# Sensly_HAT_v1_6.net
KiCad netlist of a schematic drawn in EAGLE
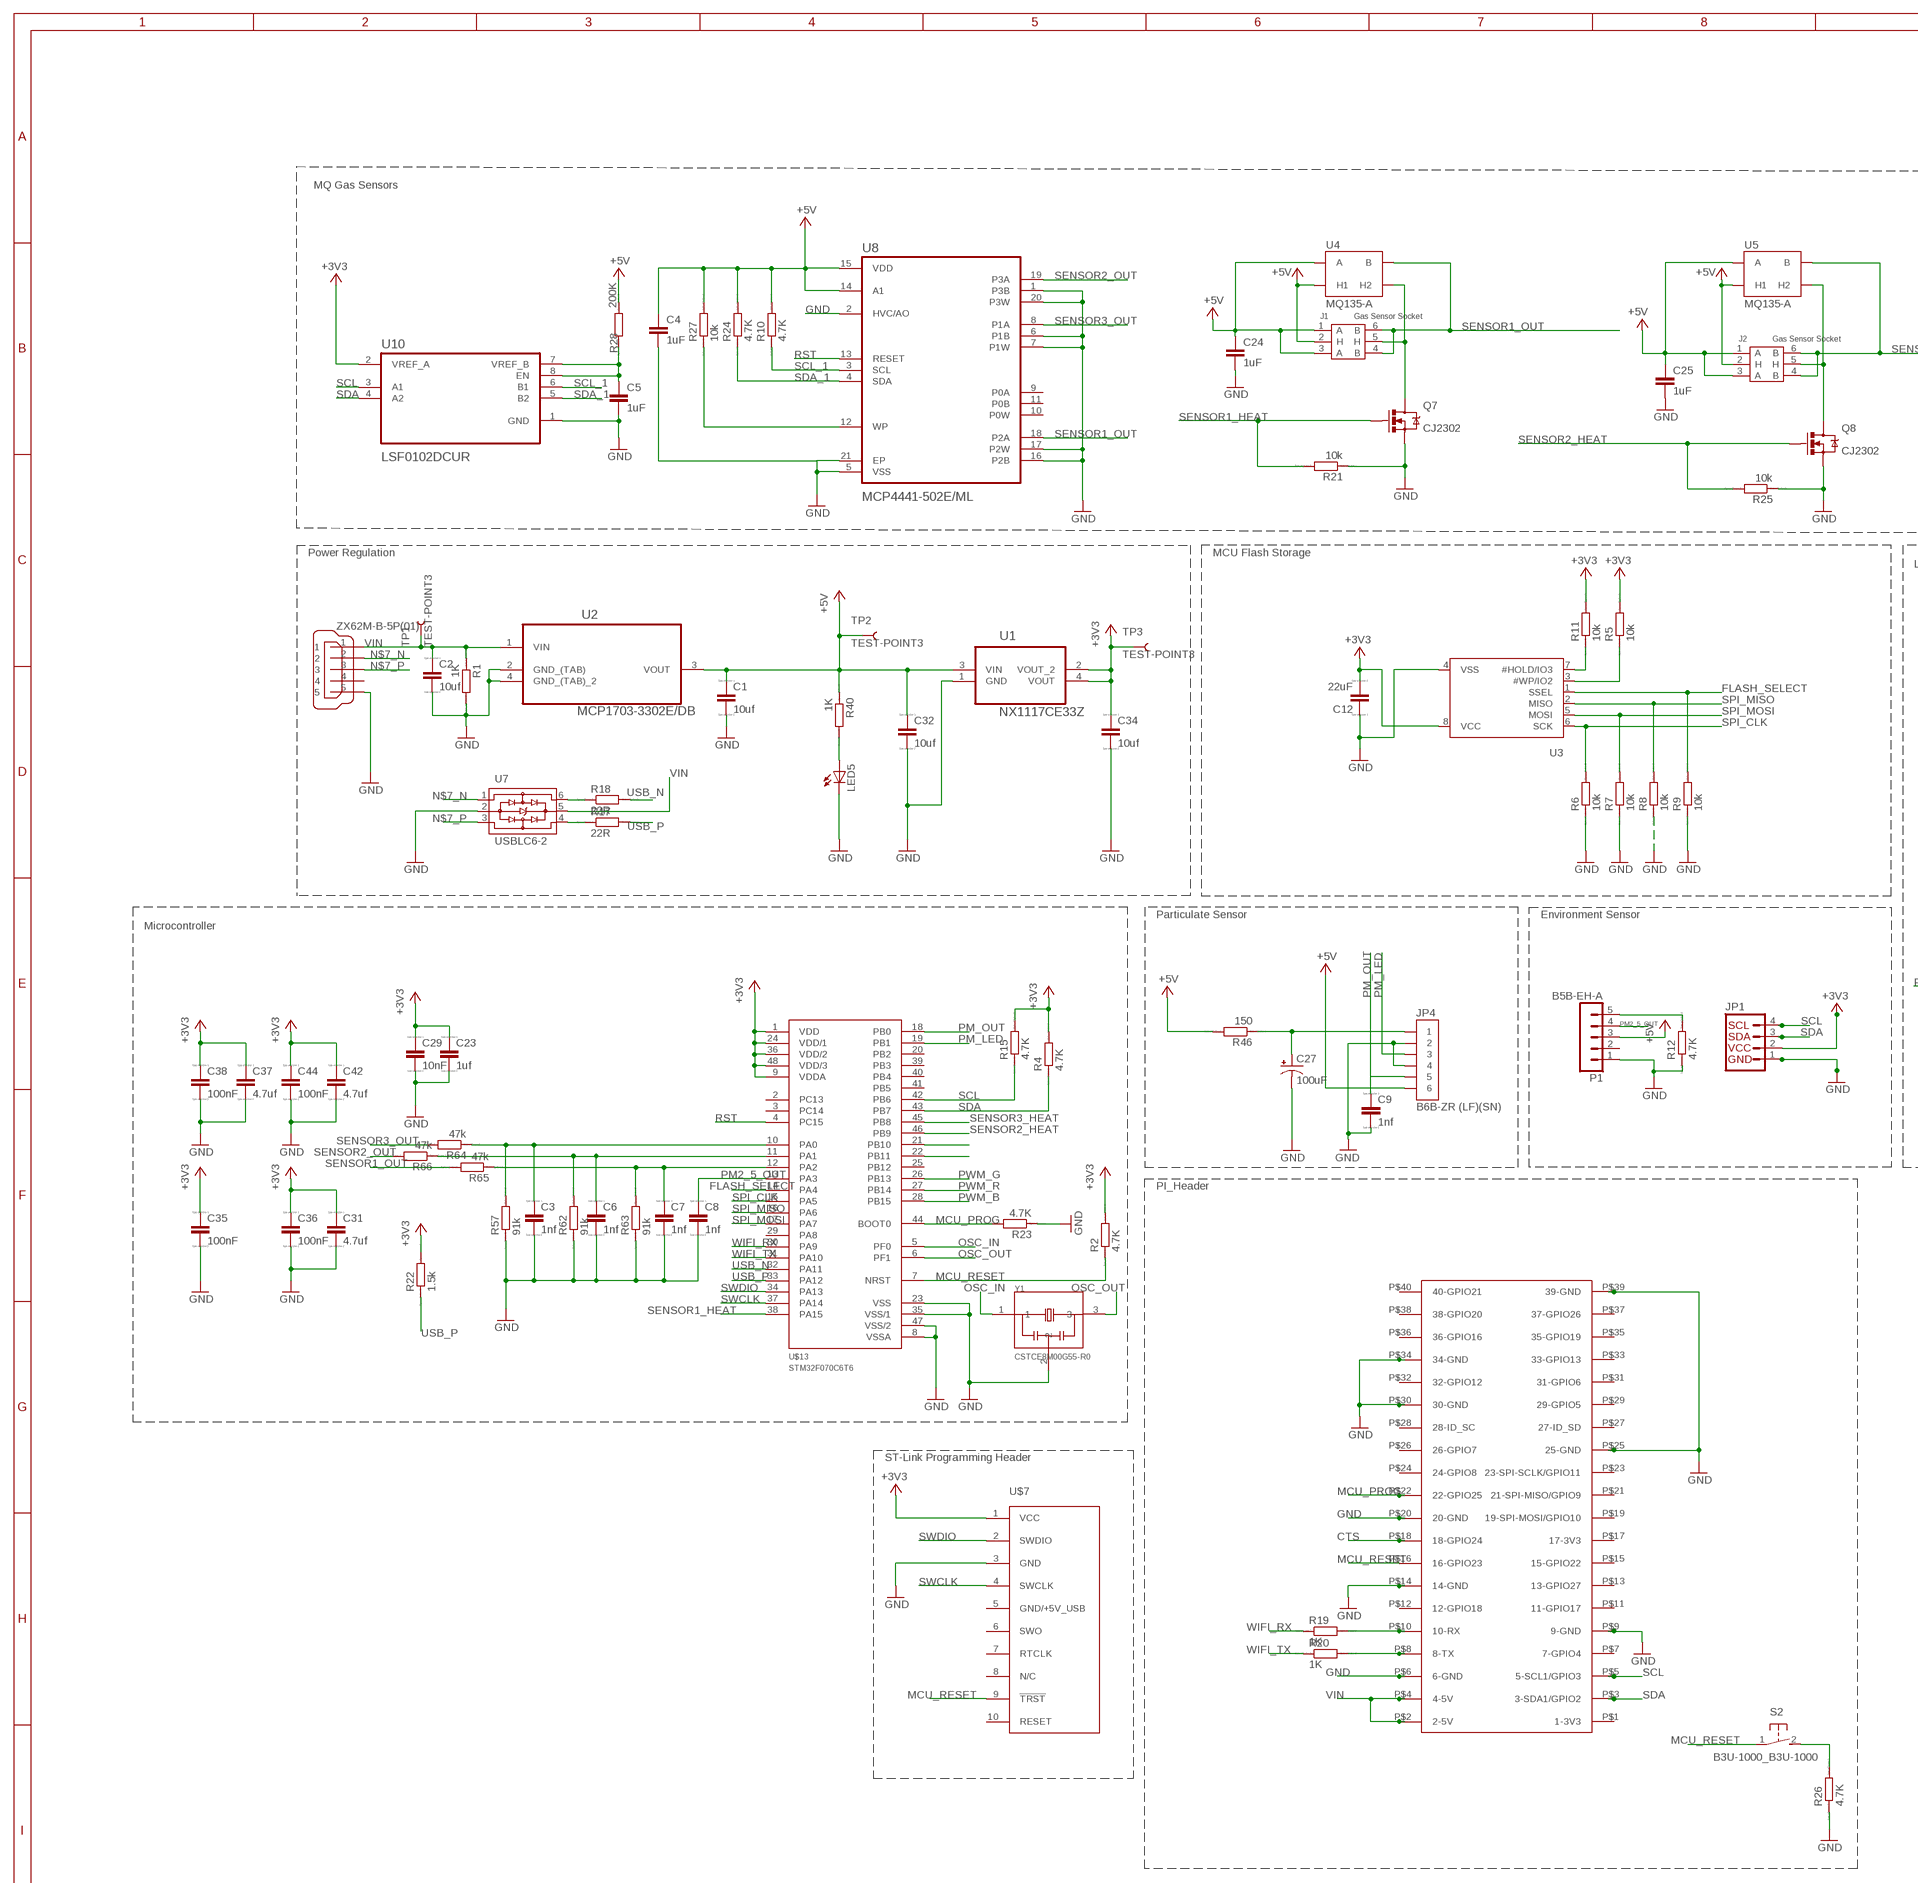
[diagram p0: schematic, sheet 1, part 1 of 2]
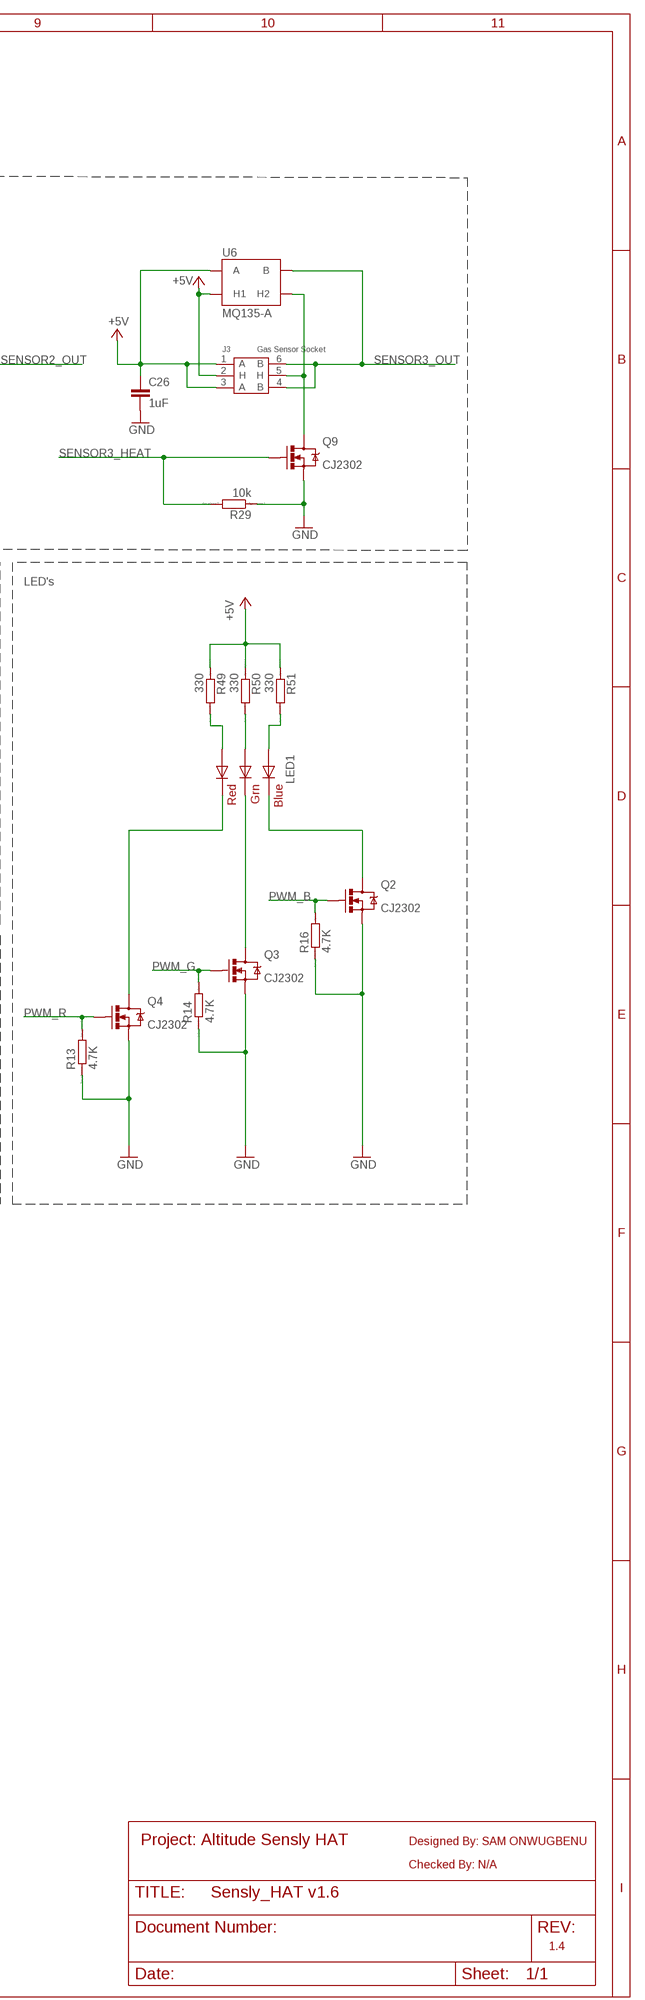
[diagram p1: schematic, sheet 1, part 2 of 2]

(export (version "E")
  (design (tool "Eeschema 10.0.6"))
  (components
    (comp (ref "C1")
      (value "10uf")
      (footprint "eagle-import:C0603")
      (libsource (lib "eagle-import") (part "CC0603"))
    )
    (comp (ref "C2")
      (value "10uf")
      (footprint "eagle-import:C0603")
      (libsource (lib "eagle-import") (part "CC0603"))
    )
    (comp (ref "C3")
      (value "1nf")
      (footprint "eagle-import:EAGLE-LTSPICE_C0402")
      (libsource (lib "eagle-import") (part "EAGLE-LTSPICE_CC0402"))
    )
    (comp (ref "C4")
      (value "1uF")
      (footprint "eagle-import:0603_N")
      (libsource (lib "eagle-import") (part "C0603"))
    )
    (comp (ref "C5")
      (value "1uF")
      (footprint "eagle-import:0603_N")
      (libsource (lib "eagle-import") (part "C0603"))
    )
    (comp (ref "C6")
      (value "1nf")
      (footprint "eagle-import:EAGLE-LTSPICE_C0402")
      (libsource (lib "eagle-import") (part "EAGLE-LTSPICE_CC0402"))
    )
    (comp (ref "C7")
      (value "1nf")
      (footprint "eagle-import:EAGLE-LTSPICE_C0402")
      (libsource (lib "eagle-import") (part "EAGLE-LTSPICE_CC0402"))
    )
    (comp (ref "C8")
      (value "1nf")
      (footprint "eagle-import:EAGLE-LTSPICE_C0402")
      (libsource (lib "eagle-import") (part "EAGLE-LTSPICE_CC0402"))
    )
    (comp (ref "C9")
      (value "1nf")
      (footprint "eagle-import:EAGLE-LTSPICE_C0402")
      (libsource (lib "eagle-import") (part "EAGLE-LTSPICE_CC0402"))
    )
    (comp (ref "C12")
      (value "22uF")
      (footprint "eagle-import:C0603")
      (libsource (lib "eagle-import") (part "CC0603"))
    )
    (comp (ref "C23")
      (value "1uf")
      (footprint "eagle-import:C0603")
      (libsource (lib "eagle-import") (part "CC0603"))
    )
    (comp (ref "C24")
      (value "1uF")
      (footprint "eagle-import:0603_N")
      (libsource (lib "eagle-import") (part "C0603"))
    )
    (comp (ref "C25")
      (value "1uF")
      (footprint "eagle-import:0603_N")
      (libsource (lib "eagle-import") (part "C0603"))
    )
    (comp (ref "C26")
      (value "1uF")
      (footprint "eagle-import:0603_N")
      (libsource (lib "eagle-import") (part "C0603"))
    )
    (comp (ref "C27")
      (value "100uF")
      (footprint "eagle-import:EIA3216")
      (libsource (lib "eagle-import") (part "CAP_POL1206"))
    )
    (comp (ref "C29")
      (value "10nF")
      (footprint "eagle-import:C0603")
      (libsource (lib "eagle-import") (part "CC0603"))
    )
    (comp (ref "C31")
      (value "4.7uf")
      (footprint "eagle-import:C0603")
      (libsource (lib "eagle-import") (part "CC0603"))
    )
    (comp (ref "C32")
      (value "10uf")
      (footprint "eagle-import:C0603")
      (libsource (lib "eagle-import") (part "CC0603"))
    )
    (comp (ref "C34")
      (value "10uf")
      (footprint "eagle-import:C0603")
      (libsource (lib "eagle-import") (part "CC0603"))
    )
    (comp (ref "C35")
      (value "100nF")
      (footprint "eagle-import:C0603")
      (libsource (lib "eagle-import") (part "CC0603"))
    )
    (comp (ref "C36")
      (value "100nF")
      (footprint "eagle-import:C0603")
      (libsource (lib "eagle-import") (part "CC0603"))
    )
    (comp (ref "C37")
      (value "4.7uf")
      (footprint "eagle-import:C0603")
      (libsource (lib "eagle-import") (part "CC0603"))
    )
    (comp (ref "C38")
      (value "100nF")
      (footprint "eagle-import:C0603")
      (libsource (lib "eagle-import") (part "CC0603"))
    )
    (comp (ref "C42")
      (value "4.7uf")
      (footprint "eagle-import:C0603")
      (libsource (lib "eagle-import") (part "CC0603"))
    )
    (comp (ref "C44")
      (value "100nF")
      (footprint "eagle-import:C0603")
      (libsource (lib "eagle-import") (part "CC0603"))
    )
    (comp (ref "J1")
      (value "Gas Sensor Socket")
      (footprint "eagle-import:6P-D17.6X9.8H")
      (libsource (lib "eagle-import") (part "MQ-SOCKET"))
    )
    (comp (ref "J2")
      (value "Gas Sensor Socket")
      (footprint "eagle-import:6P-D17.6X9.8H")
      (libsource (lib "eagle-import") (part "MQ-SOCKET"))
    )
    (comp (ref "J3")
      (value "Gas Sensor Socket")
      (footprint "eagle-import:6P-D17.6X9.8H")
      (libsource (lib "eagle-import") (part "MQ-SOCKET"))
    )
    (comp (ref "JP1")
      (value "I2C_STANDARD")
      (footprint "eagle-import:1X04")
      (libsource (lib "eagle-import") (part "I2C_STANDARD"))
    )
    (comp (ref "JP4")
      (value "B6B-ZR (LF)(SN)")
      (footprint "eagle-import:CONNECTOR_B6B-ZR")
      (libsource (lib "eagle-import") (part "CONNECTOR_6X1-ZR-THT"))
    )
    (comp (ref "LED1")
      (value "RGBLED5050")
      (footprint "eagle-import:RGBLED5050")
      (libsource (lib "eagle-import") (part "RGBLED5050"))
    )
    (comp (ref "LED5")
      (value "LEDCHIPLED_0603")
      (footprint "eagle-import:CHIPLED_0603")
      (libsource (lib "eagle-import") (part "LEDCHIPLED_0603"))
    )
    (comp (ref "P1")
      (value "B5B-EH-A")
      (footprint "eagle-import:B5B-EH-A")
      (libsource (lib "eagle-import") (part "B5B-EH-A"))
    )
    (comp (ref "Q2")
      (value "CJ2302")
      (footprint "eagle-import:SOT-23-3_N_SSOT-3_N")
      (libsource (lib "eagle-import") (part "MOSFET_N_SOT23-3"))
    )
    (comp (ref "Q3")
      (value "CJ2302")
      (footprint "eagle-import:SOT-23-3_N_SSOT-3_N")
      (libsource (lib "eagle-import") (part "MOSFET_N_SOT23-3"))
    )
    (comp (ref "Q4")
      (value "CJ2302")
      (footprint "eagle-import:SOT-23-3_N_SSOT-3_N")
      (libsource (lib "eagle-import") (part "MOSFET_N_SOT23-3"))
    )
    (comp (ref "Q7")
      (value "CJ2302")
      (footprint "eagle-import:SOT-23-3_N_SSOT-3_N")
      (libsource (lib "eagle-import") (part "MOSFET_N_SOT23-3"))
    )
    (comp (ref "Q8")
      (value "CJ2302")
      (footprint "eagle-import:SOT-23-3_N_SSOT-3_N")
      (libsource (lib "eagle-import") (part "MOSFET_N_SOT23-3"))
    )
    (comp (ref "Q9")
      (value "CJ2302")
      (footprint "eagle-import:SOT-23-3_N_SSOT-3_N")
      (libsource (lib "eagle-import") (part "MOSFET_N_SOT23-3"))
    )
    (comp (ref "R1")
      (value "1K")
      (footprint "eagle-import:R0603")
      (libsource (lib "eagle-import") (part "RR0603"))
    )
    (comp (ref "R2")
      (value "4.7K")
      (footprint "eagle-import:R0603")
      (libsource (lib "eagle-import") (part "RR0603"))
    )
    (comp (ref "R4")
      (value "4.7K")
      (footprint "eagle-import:R0603")
      (libsource (lib "eagle-import") (part "RR0603"))
    )
    (comp (ref "R5")
      (value "10k")
      (footprint "eagle-import:R0603")
      (libsource (lib "eagle-import") (part "RR0603"))
    )
    (comp (ref "R6")
      (value "10k")
      (footprint "eagle-import:R0603")
      (libsource (lib "eagle-import") (part "RR0603"))
    )
    (comp (ref "R7")
      (value "10k")
      (footprint "eagle-import:R0603")
      (libsource (lib "eagle-import") (part "RR0603"))
    )
    (comp (ref "R8")
      (value "10k")
      (footprint "eagle-import:R0603")
      (libsource (lib "eagle-import") (part "RR0603"))
    )
    (comp (ref "R9")
      (value "10k")
      (footprint "eagle-import:R0603")
      (libsource (lib "eagle-import") (part "RR0603"))
    )
    (comp (ref "R10")
      (value "4.7K")
      (footprint "eagle-import:R0603")
      (libsource (lib "eagle-import") (part "RR0603"))
    )
    (comp (ref "R11")
      (value "10k")
      (footprint "eagle-import:R0603")
      (libsource (lib "eagle-import") (part "RR0603"))
    )
    (comp (ref "R12")
      (value "4.7K")
      (footprint "eagle-import:R0603")
      (libsource (lib "eagle-import") (part "RR0603"))
    )
    (comp (ref "R13")
      (value "4.7K")
      (footprint "eagle-import:R0603")
      (libsource (lib "eagle-import") (part "RR0603"))
    )
    (comp (ref "R14")
      (value "4.7K")
      (footprint "eagle-import:R0603")
      (libsource (lib "eagle-import") (part "RR0603"))
    )
    (comp (ref "R15")
      (value "4.7K")
      (footprint "eagle-import:R0603")
      (libsource (lib "eagle-import") (part "RR0603"))
    )
    (comp (ref "R16")
      (value "4.7K")
      (footprint "eagle-import:R0603")
      (libsource (lib "eagle-import") (part "RR0603"))
    )
    (comp (ref "R17")
      (value "22R")
      (footprint "eagle-import:R0603")
      (libsource (lib "eagle-import") (part "RR0603"))
    )
    (comp (ref "R18")
      (value "22R")
      (footprint "eagle-import:R0603")
      (libsource (lib "eagle-import") (part "RR0603"))
    )
    (comp (ref "R19")
      (value "1K")
      (footprint "eagle-import:R0603")
      (libsource (lib "eagle-import") (part "RR0603"))
    )
    (comp (ref "R20")
      (value "1K")
      (footprint "eagle-import:R0603")
      (libsource (lib "eagle-import") (part "RR0603"))
    )
    (comp (ref "R21")
      (value "10k")
      (footprint "eagle-import:R0603")
      (libsource (lib "eagle-import") (part "RR0603"))
    )
    (comp (ref "R22")
      (value "1.5k")
      (footprint "eagle-import:R0603")
      (libsource (lib "eagle-import") (part "RR0603"))
    )
    (comp (ref "R23")
      (value "4.7K")
      (footprint "eagle-import:R0603")
      (libsource (lib "eagle-import") (part "RR0603"))
    )
    (comp (ref "R24")
      (value "4.7K")
      (footprint "eagle-import:R0603")
      (libsource (lib "eagle-import") (part "RR0603"))
    )
    (comp (ref "R25")
      (value "10k")
      (footprint "eagle-import:R0603")
      (libsource (lib "eagle-import") (part "RR0603"))
    )
    (comp (ref "R26")
      (value "4.7K")
      (footprint "eagle-import:R0603")
      (libsource (lib "eagle-import") (part "RR0603"))
    )
    (comp (ref "R27")
      (value "10k")
      (footprint "eagle-import:R0603")
      (libsource (lib "eagle-import") (part "RR0603"))
    )
    (comp (ref "R28")
      (value "200K")
      (footprint "eagle-import:R0603")
      (libsource (lib "eagle-import") (part "RR0603"))
    )
    (comp (ref "R29")
      (value "10k")
      (footprint "eagle-import:R0603")
      (libsource (lib "eagle-import") (part "RR0603"))
    )
    (comp (ref "R40")
      (value "1K")
      (footprint "eagle-import:R0603")
      (libsource (lib "eagle-import") (part "RR0603"))
    )
    (comp (ref "R46")
      (value "150")
      (footprint "eagle-import:R0603")
      (libsource (lib "eagle-import") (part "RR0603"))
    )
    (comp (ref "R49")
      (value "330")
      (footprint "eagle-import:R0603")
      (libsource (lib "eagle-import") (part "RR0603"))
    )
    (comp (ref "R50")
      (value "330")
      (footprint "eagle-import:R0603")
      (libsource (lib "eagle-import") (part "RR0603"))
    )
    (comp (ref "R51")
      (value "330")
      (footprint "eagle-import:R0603")
      (libsource (lib "eagle-import") (part "RR0603"))
    )
    (comp (ref "R57")
      (value "91k")
      (footprint "eagle-import:R0603")
      (libsource (lib "eagle-import") (part "RR0603"))
    )
    (comp (ref "R62")
      (value "91k")
      (footprint "eagle-import:R0603")
      (libsource (lib "eagle-import") (part "RR0603"))
    )
    (comp (ref "R63")
      (value "91k")
      (footprint "eagle-import:R0603")
      (libsource (lib "eagle-import") (part "RR0603"))
    )
    (comp (ref "R64")
      (value "47k")
      (footprint "eagle-import:R0603")
      (libsource (lib "eagle-import") (part "RR0603"))
    )
    (comp (ref "R65")
      (value "47k")
      (footprint "eagle-import:R0603")
      (libsource (lib "eagle-import") (part "RR0603"))
    )
    (comp (ref "R66")
      (value "47k")
      (footprint "eagle-import:R0603")
      (libsource (lib "eagle-import") (part "RR0603"))
    )
    (comp (ref "S2")
      (value "B3U-1000_B3U-1000")
      (footprint "eagle-import:B3U-1000_B3U")
      (libsource (lib "eagle-import") (part "B3U-1000_B3U-1000"))
    )
    (comp (ref "TP1")
      (value "TEST-POINT3")
      (footprint "eagle-import:PAD.03X.03")
      (libsource (lib "eagle-import") (part "TEST-POINT3"))
    )
    (comp (ref "TP2")
      (value "TEST-POINT3")
      (footprint "eagle-import:PAD.03X.03")
      (libsource (lib "eagle-import") (part "TEST-POINT3"))
    )
    (comp (ref "TP3")
      (value "TEST-POINT3")
      (footprint "eagle-import:PAD.03X.03")
      (libsource (lib "eagle-import") (part "TEST-POINT3"))
    )
    (comp (ref "U$2")
      (value "RASPBERRY-PI+")
      (footprint "eagle-import:RASPBERRY-PI-PLUS-CAM_NOTCH")
      (libsource (lib "eagle-import") (part "RASPBERRY-PI+"))
    )
    (comp (ref "U$7")
      (value "TC2050-MCP-NL")
      (footprint "eagle-import:TC2030-MCP-NL")
      (libsource (lib "eagle-import") (part "TC2050-MCP-NL"))
    )
    (comp (ref "U$9")
      (value "ZX62M-B-5P(01)")
      (footprint "eagle-import:MICROUSB")
      (libsource (lib "eagle-import") (part "ZX62M-B-5P(01)"))
    )
    (comp (ref "U$13")
      (value "STM32F070C6T6")
      (footprint "eagle-import:QFP50P900X900X160-48N")
      (libsource (lib "eagle-import") (part "STM32F070C6T6"))
    )
    (comp (ref "U1")
      (value "NX1117CE33Z")
      (footprint "eagle-import:SOT230P700X180-4N")
      (libsource (lib "eagle-import") (part "NX1117CE33Z"))
    )
    (comp (ref "U2")
      (value "MCP1703-3302E/DB")
      (footprint "eagle-import:SOT230P700X180-4N")
      (libsource (lib "eagle-import") (part "MCP1703-3302E/DB"))
    )
    (comp (ref "U3")
      (value "SPIFLASH_SOIC8")
      (footprint "eagle-import:SOIC8_150MIL")
      (libsource (lib "eagle-import") (part "SPIFLASH_SOIC8"))
    )
    (comp (ref "U4")
      (value "MQ135-A")
      (footprint "eagle-import:MQ135-A")
      (libsource (lib "eagle-import") (part "MQ135-A"))
    )
    (comp (ref "U5")
      (value "MQ135-A")
      (footprint "eagle-import:MQ135-A")
      (libsource (lib "eagle-import") (part "MQ135-A"))
    )
    (comp (ref "U6")
      (value "MQ135-A")
      (footprint "eagle-import:MQ135-A")
      (libsource (lib "eagle-import") (part "MQ135-A"))
    )
    (comp (ref "U7")
      (value "USBLC6-2")
      (footprint "eagle-import:USBLC6-2P6")
      (fields (field (name "MF") "STMicroelectronics"))
      (libsource (lib "eagle-import") (part "USBLC6-2"))
    )
    (comp (ref "U8")
      (value "MCP4441-502E/ML")
      (footprint "eagle-import:QFN50P400X400X100-21N")
      (fields (field (name "MF") "Microchip"))
      (libsource (lib "eagle-import") (part "MCP4441-502E/ML"))
    )
    (comp (ref "U10")
      (value "LSF0102DCUR")
      (footprint "eagle-import:SOP50P310X90-8N")
      (fields (field (name "MF") "Texas Instruments"))
      (libsource (lib "eagle-import") (part "LSF0102DCUR"))
    )
    (comp (ref "Y1")
      (value "CSTCE8M00G55-R0")
      (footprint "eagle-import:OSC_CSTCE8M00G55-R0")
      (fields (field (name "MF") "Murata"))
      (libsource (lib "eagle-import") (part "CSTCE8M00G55-R0"))
    )
  )
  (nets
    (net (code "1") (name "+3V3") (class "Default")
      (node (ref "C12") (pin "2") (pinfunction "2_2") (pintype "passive"))
      (node (ref "C23") (pin "1") (pinfunction "1_1") (pintype "passive"))
      (node (ref "C29") (pin "1") (pinfunction "1_1") (pintype "passive"))
      (node (ref "C31") (pin "1") (pinfunction "1_1") (pintype "passive"))
      (node (ref "C34") (pin "1") (pinfunction "1_1") (pintype "passive"))
      (node (ref "C35") (pin "1") (pinfunction "1_1") (pintype "passive"))
      (node (ref "C36") (pin "1") (pinfunction "1_1") (pintype "passive"))
      (node (ref "C37") (pin "1") (pinfunction "1_1") (pintype "passive"))
      (node (ref "C38") (pin "1") (pinfunction "1_1") (pintype "passive"))
      (node (ref "C42") (pin "1") (pinfunction "1_1") (pintype "passive"))
      (node (ref "C44") (pin "1") (pinfunction "1_1") (pintype "passive"))
      (node (ref "JP1") (pin "2") (pinfunction "2_2") (pintype "passive"))
      (node (ref "R11") (pin "2") (pinfunction "2_2") (pintype "passive"))
      (node (ref "R15") (pin "2") (pinfunction "2_2") (pintype "passive"))
      (node (ref "R2") (pin "2") (pinfunction "2_2") (pintype "passive"))
      (node (ref "R22") (pin "2") (pinfunction "2_2") (pintype "passive"))
      (node (ref "R4") (pin "2") (pinfunction "2_2") (pintype "passive"))
      (node (ref "R5") (pin "2") (pinfunction "2_2") (pintype "passive"))
      (node (ref "TP3") (pin "P$1") (pinfunction "1_P$1") (pintype "bidirectional"))
      (node (ref "U$13") (pin "1") (pinfunction "VDD_1") (pintype "bidirectional"))
      (node (ref "U$13") (pin "24") (pinfunction "VDD/1_24") (pintype "bidirectional"))
      (node (ref "U$13") (pin "36") (pinfunction "VDD/2_36") (pintype "bidirectional"))
      (node (ref "U$13") (pin "48") (pinfunction "VDD/3_48") (pintype "bidirectional"))
      (node (ref "U$13") (pin "9") (pinfunction "VDDA_9") (pintype "bidirectional"))
      (node (ref "U$7") (pin "1") (pinfunction "VCC_1") (pintype "bidirectional"))
      (node (ref "U1") (pin "2") (pinfunction "VOUT_2_2") (pintype "output"))
      (node (ref "U1") (pin "4") (pinfunction "VOUT_4") (pintype "output"))
      (node (ref "U10") (pin "2") (pinfunction "VREF_A_2") (pintype "input"))
      (node (ref "U3") (pin "8") (pinfunction "VCC_8") (pintype "bidirectional"))
    )
    (net (code "2") (name "+5V") (class "Default")
      (node (ref "C1") (pin "1") (pinfunction "1_1") (pintype "passive"))
      (node (ref "C24") (pin "1") (pinfunction "1_1") (pintype "passive"))
      (node (ref "C25") (pin "1") (pinfunction "1_1") (pintype "passive"))
      (node (ref "C26") (pin "1") (pinfunction "1_1") (pintype "passive"))
      (node (ref "C32") (pin "1") (pinfunction "1_1") (pintype "passive"))
      (node (ref "C4") (pin "1") (pinfunction "1_1") (pintype "passive"))
      (node (ref "J1") (pin "1") (pinfunction "A_1") (pintype "bidirectional"))
      (node (ref "J1") (pin "2") (pinfunction "H_2") (pintype "bidirectional"))
      (node (ref "J1") (pin "3") (pinfunction "A_3") (pintype "bidirectional"))
      (node (ref "J2") (pin "1") (pinfunction "A_1") (pintype "bidirectional"))
      (node (ref "J2") (pin "2") (pinfunction "H_2") (pintype "bidirectional"))
      (node (ref "J2") (pin "3") (pinfunction "A_3") (pintype "bidirectional"))
      (node (ref "J3") (pin "1") (pinfunction "A_1") (pintype "bidirectional"))
      (node (ref "J3") (pin "2") (pinfunction "H_2") (pintype "bidirectional"))
      (node (ref "J3") (pin "3") (pinfunction "A_3") (pintype "bidirectional"))
      (node (ref "JP4") (pin "P$6") (pinfunction "6_P$6") (pintype "bidirectional"))
      (node (ref "P1") (pin "3") (pinfunction "3_3") (pintype "passive"))
      (node (ref "R10") (pin "2") (pinfunction "2_2") (pintype "passive"))
      (node (ref "R24") (pin "2") (pinfunction "2_2") (pintype "passive"))
      (node (ref "R27") (pin "2") (pinfunction "2_2") (pintype "passive"))
      (node (ref "R28") (pin "2") (pinfunction "2_2") (pintype "passive"))
      (node (ref "R40") (pin "1") (pinfunction "1_1") (pintype "passive"))
      (node (ref "R46") (pin "2") (pinfunction "2_2") (pintype "passive"))
      (node (ref "R49") (pin "1") (pinfunction "1_1") (pintype "passive"))
      (node (ref "R50") (pin "1") (pinfunction "1_1") (pintype "passive"))
      (node (ref "R51") (pin "1") (pinfunction "1_1") (pintype "passive"))
      (node (ref "TP2") (pin "P$1") (pinfunction "1_P$1") (pintype "bidirectional"))
      (node (ref "U1") (pin "3") (pinfunction "VIN_3") (pintype "power_in"))
      (node (ref "U2") (pin "3") (pinfunction "VOUT_3") (pintype "output"))
      (node (ref "U4") (pin "1") (pinfunction "A_1") (pintype "bidirectional"))
      (node (ref "U4") (pin "2") (pinfunction "H1_2") (pintype "bidirectional"))
      (node (ref "U4") (pin "3") (pinfunction "A_3") (pintype "bidirectional"))
      (node (ref "U5") (pin "1") (pinfunction "A_1") (pintype "bidirectional"))
      (node (ref "U5") (pin "2") (pinfunction "H1_2") (pintype "bidirectional"))
      (node (ref "U5") (pin "3") (pinfunction "A_3") (pintype "bidirectional"))
      (node (ref "U6") (pin "1") (pinfunction "A_1") (pintype "bidirectional"))
      (node (ref "U6") (pin "2") (pinfunction "H1_2") (pintype "bidirectional"))
      (node (ref "U6") (pin "3") (pinfunction "A_3") (pintype "bidirectional"))
      (node (ref "U8") (pin "14") (pinfunction "A1_14") (pintype "input"))
      (node (ref "U8") (pin "15") (pinfunction "VDD_15") (pintype "power_in"))
    )
    (net (code "3") (name "/CTS") (class "Default")
      (node (ref "U$2") (pin "P$18") (pinfunction "18-GPIO24_P$18") (pintype "bidirectional"))
    )
    (net (code "4") (name "/FLASH_SELECT") (class "Default")
      (node (ref "R9") (pin "2") (pinfunction "2_2") (pintype "passive"))
      (node (ref "U$13") (pin "14") (pinfunction "PA4_14") (pintype "bidirectional"))
      (node (ref "U3") (pin "1") (pinfunction "SSEL_1") (pintype "bidirectional"))
    )
    (net (code "5") (name "/MCU_PROG") (class "Default")
      (node (ref "R23") (pin "2") (pinfunction "2_2") (pintype "passive"))
      (node (ref "U$13") (pin "44") (pinfunction "BOOT0_44") (pintype "bidirectional"))
      (node (ref "U$2") (pin "P$22") (pinfunction "22-GPIO25_P$22") (pintype "bidirectional"))
    )
    (net (code "6") (name "/MCU_RESET") (class "Default")
      (node (ref "R2") (pin "1") (pinfunction "1_1") (pintype "passive"))
      (node (ref "S2") (pin "1") (pinfunction "1_1") (pintype "passive"))
      (node (ref "U$13") (pin "7") (pinfunction "NRST_7") (pintype "bidirectional"))
      (node (ref "U$2") (pin "P$16") (pinfunction "16-GPIO23_P$16") (pintype "bidirectional"))
      (node (ref "U$7") (pin "9") (pinfunction "~{TRST}_9") (pintype "bidirectional"))
    )
    (net (code "7") (name "/N$7_N") (class "Default")
      (node (ref "U$9") (pin "2") (pinfunction "2_2") (pintype "bidirectional"))
      (node (ref "U7") (pin "1") (pinfunction "1_1") (pintype "bidirectional"))
    )
    (net (code "8") (name "/N$7_P") (class "Default")
      (node (ref "U$9") (pin "3") (pinfunction "3_3") (pintype "bidirectional"))
      (node (ref "U7") (pin "3") (pinfunction "3_3") (pintype "bidirectional"))
    )
    (net (code "9") (name "/OSC_IN") (class "Default")
      (node (ref "U$13") (pin "5") (pinfunction "PF0_5") (pintype "bidirectional"))
      (node (ref "Y1") (pin "1") (pinfunction "1_1") (pintype "passive"))
    )
    (net (code "10") (name "/OSC_OUT") (class "Default")
      (node (ref "U$13") (pin "6") (pinfunction "PF1_6") (pintype "bidirectional"))
      (node (ref "Y1") (pin "3") (pinfunction "3_3") (pintype "passive"))
    )
    (net (code "11") (name "/PM2_5_OUT") (class "Default")
      (node (ref "C8") (pin "1") (pinfunction "1_1") (pintype "passive"))
      (node (ref "P1") (pin "4") (pinfunction "4_4") (pintype "passive"))
      (node (ref "U$13") (pin "13") (pinfunction "PA3_13") (pintype "bidirectional"))
    )
    (net (code "12") (name "/PM_LED") (class "Default")
      (node (ref "JP4") (pin "P$3") (pinfunction "3_P$3") (pintype "bidirectional"))
      (node (ref "U$13") (pin "19") (pinfunction "PB1_19") (pintype "bidirectional"))
    )
    (net (code "13") (name "/PM_OUT") (class "Default")
      (node (ref "C9") (pin "1") (pinfunction "1_1") (pintype "passive"))
      (node (ref "JP4") (pin "P$5") (pinfunction "5_P$5") (pintype "bidirectional"))
      (node (ref "U$13") (pin "18") (pinfunction "PB0_18") (pintype "bidirectional"))
    )
    (net (code "14") (name "/PWM_B") (class "Default")
      (node (ref "Q2") (pin "1") (pinfunction "G_1") (pintype "passive"))
      (node (ref "R16") (pin "2") (pinfunction "2_2") (pintype "passive"))
      (node (ref "U$13") (pin "28") (pinfunction "PB15_28") (pintype "bidirectional"))
    )
    (net (code "15") (name "/PWM_G") (class "Default")
      (node (ref "Q3") (pin "1") (pinfunction "G_1") (pintype "passive"))
      (node (ref "R14") (pin "2") (pinfunction "2_2") (pintype "passive"))
      (node (ref "U$13") (pin "26") (pinfunction "PB13_26") (pintype "bidirectional"))
    )
    (net (code "16") (name "/PWM_R") (class "Default")
      (node (ref "Q4") (pin "1") (pinfunction "G_1") (pintype "passive"))
      (node (ref "R13") (pin "2") (pinfunction "2_2") (pintype "passive"))
      (node (ref "U$13") (pin "27") (pinfunction "PB14_27") (pintype "bidirectional"))
    )
    (net (code "17") (name "/RST") (class "Default")
      (node (ref "U$13") (pin "4") (pinfunction "PC15_4") (pintype "bidirectional"))
      (node (ref "U8") (pin "13") (pinfunction "RESET_13") (pintype "input"))
    )
    (net (code "18") (name "/SCL") (class "Default")
      (node (ref "JP1") (pin "4") (pinfunction "4_4") (pintype "passive"))
      (node (ref "R15") (pin "1") (pinfunction "1_1") (pintype "passive"))
      (node (ref "U$13") (pin "42") (pinfunction "PB6_42") (pintype "bidirectional"))
      (node (ref "U$2") (pin "P$5") (pinfunction "5-SCL1/GPIO3_P$5") (pintype "bidirectional"))
      (node (ref "U10") (pin "3") (pinfunction "A1_3") (pintype "input"))
    )
    (net (code "19") (name "/SCL_1") (class "Default")
      (node (ref "R10") (pin "1") (pinfunction "1_1") (pintype "passive"))
      (node (ref "U10") (pin "6") (pinfunction "B1_6") (pintype "output"))
      (node (ref "U8") (pin "3") (pinfunction "SCL_3") (pintype "input"))
    )
    (net (code "20") (name "/SDA") (class "Default")
      (node (ref "JP1") (pin "3") (pinfunction "3_3") (pintype "passive"))
      (node (ref "R4") (pin "1") (pinfunction "1_1") (pintype "passive"))
      (node (ref "U$13") (pin "43") (pinfunction "PB7_43") (pintype "bidirectional"))
      (node (ref "U$2") (pin "P$3") (pinfunction "3-SDA1/GPIO2_P$3") (pintype "bidirectional"))
      (node (ref "U10") (pin "4") (pinfunction "A2_4") (pintype "input"))
    )
    (net (code "21") (name "/SDA_1") (class "Default")
      (node (ref "R24") (pin "1") (pinfunction "1_1") (pintype "passive"))
      (node (ref "U10") (pin "5") (pinfunction "B2_5") (pintype "output"))
      (node (ref "U8") (pin "4") (pinfunction "SDA_4") (pintype "input"))
    )
    (net (code "22") (name "/SENSOR1_HEAT") (class "Default")
      (node (ref "Q7") (pin "1") (pinfunction "G_1") (pintype "passive"))
      (node (ref "R21") (pin "2") (pinfunction "2_2") (pintype "passive"))
      (node (ref "U$13") (pin "38") (pinfunction "PA15_38") (pintype "bidirectional"))
    )
    (net (code "23") (name "/SENSOR1_OUT") (class "Default")
      (node (ref "J1") (pin "4") (pinfunction "B_4") (pintype "bidirectional"))
      (node (ref "J1") (pin "6") (pinfunction "B_6") (pintype "bidirectional"))
      (node (ref "R65") (pin "2") (pinfunction "2_2") (pintype "passive"))
      (node (ref "U4") (pin "4") (pinfunction "B_4") (pintype "bidirectional"))
      (node (ref "U4") (pin "6") (pinfunction "B_6") (pintype "bidirectional"))
      (node (ref "U8") (pin "18") (pinfunction "P2A_18") (pintype "bidirectional"))
    )
    (net (code "24") (name "/SENSOR2_HEAT") (class "Default")
      (node (ref "Q8") (pin "1") (pinfunction "G_1") (pintype "passive"))
      (node (ref "R25") (pin "2") (pinfunction "2_2") (pintype "passive"))
      (node (ref "U$13") (pin "46") (pinfunction "PB9_46") (pintype "bidirectional"))
    )
    (net (code "25") (name "/SENSOR2_OUT") (class "Default")
      (node (ref "J2") (pin "4") (pinfunction "B_4") (pintype "bidirectional"))
      (node (ref "J2") (pin "6") (pinfunction "B_6") (pintype "bidirectional"))
      (node (ref "R66") (pin "2") (pinfunction "2_2") (pintype "passive"))
      (node (ref "U5") (pin "4") (pinfunction "B_4") (pintype "bidirectional"))
      (node (ref "U5") (pin "6") (pinfunction "B_6") (pintype "bidirectional"))
      (node (ref "U8") (pin "19") (pinfunction "P3A_19") (pintype "bidirectional"))
    )
    (net (code "26") (name "/SENSOR3_HEAT") (class "Default")
      (node (ref "Q9") (pin "1") (pinfunction "G_1") (pintype "passive"))
      (node (ref "R29") (pin "2") (pinfunction "2_2") (pintype "passive"))
      (node (ref "U$13") (pin "45") (pinfunction "PB8_45") (pintype "bidirectional"))
    )
    (net (code "27") (name "/SENSOR3_OUT") (class "Default")
      (node (ref "J3") (pin "4") (pinfunction "B_4") (pintype "bidirectional"))
      (node (ref "J3") (pin "6") (pinfunction "B_6") (pintype "bidirectional"))
      (node (ref "R64") (pin "2") (pinfunction "2_2") (pintype "passive"))
      (node (ref "U6") (pin "4") (pinfunction "B_4") (pintype "bidirectional"))
      (node (ref "U6") (pin "6") (pinfunction "B_6") (pintype "bidirectional"))
      (node (ref "U8") (pin "8") (pinfunction "P1A_8") (pintype "bidirectional"))
    )
    (net (code "28") (name "/SPI_CLK") (class "Default")
      (node (ref "R6") (pin "2") (pinfunction "2_2") (pintype "passive"))
      (node (ref "U$13") (pin "15") (pinfunction "PA5_15") (pintype "bidirectional"))
      (node (ref "U3") (pin "6") (pinfunction "SCK_6") (pintype "bidirectional"))
    )
    (net (code "29") (name "/SPI_MISO") (class "Default")
      (node (ref "R8") (pin "2") (pinfunction "2_2") (pintype "passive"))
      (node (ref "U$13") (pin "16") (pinfunction "PA6_16") (pintype "bidirectional"))
      (node (ref "U3") (pin "2") (pinfunction "MISO_2") (pintype "bidirectional"))
    )
    (net (code "30") (name "/SPI_MOSI") (class "Default")
      (node (ref "R7") (pin "2") (pinfunction "2_2") (pintype "passive"))
      (node (ref "U$13") (pin "17") (pinfunction "PA7_17") (pintype "bidirectional"))
      (node (ref "U3") (pin "5") (pinfunction "MOSI_5") (pintype "bidirectional"))
    )
    (net (code "31") (name "/SWCLK") (class "Default")
      (node (ref "U$13") (pin "37") (pinfunction "PA14_37") (pintype "bidirectional"))
      (node (ref "U$7") (pin "4") (pinfunction "SWCLK_4") (pintype "bidirectional"))
    )
    (net (code "32") (name "/SWDIO") (class "Default")
      (node (ref "U$13") (pin "34") (pinfunction "PA13_34") (pintype "bidirectional"))
      (node (ref "U$7") (pin "2") (pinfunction "SWDIO_2") (pintype "bidirectional"))
    )
    (net (code "33") (name "/USB_N") (class "Default")
      (node (ref "R18") (pin "2") (pinfunction "2_2") (pintype "passive"))
      (node (ref "U$13") (pin "32") (pinfunction "PA11_32") (pintype "bidirectional"))
    )
    (net (code "34") (name "/USB_P") (class "Default")
      (node (ref "R17") (pin "2") (pinfunction "2_2") (pintype "passive"))
      (node (ref "R22") (pin "1") (pinfunction "1_1") (pintype "passive"))
      (node (ref "U$13") (pin "33") (pinfunction "PA12_33") (pintype "bidirectional"))
    )
    (net (code "35") (name "/VIN") (class "Default")
      (node (ref "C2") (pin "1") (pinfunction "1_1") (pintype "passive"))
      (node (ref "R1") (pin "1") (pinfunction "1_1") (pintype "passive"))
      (node (ref "TP1") (pin "P$1") (pinfunction "1_P$1") (pintype "bidirectional"))
      (node (ref "U$2") (pin "P$2") (pinfunction "2-5V_P$2") (pintype "bidirectional"))
      (node (ref "U$2") (pin "P$4") (pinfunction "4-5V_P$4") (pintype "bidirectional"))
      (node (ref "U$9") (pin "1") (pinfunction "1_1") (pintype "bidirectional"))
      (node (ref "U2") (pin "1") (pinfunction "VIN_1") (pintype "input"))
      (node (ref "U7") (pin "5") (pinfunction "5_5") (pintype "power_in"))
    )
    (net (code "36") (name "/WIFI_RX") (class "Default")
      (node (ref "R19") (pin "1") (pinfunction "1_1") (pintype "passive"))
      (node (ref "U$13") (pin "30") (pinfunction "PA9_30") (pintype "bidirectional"))
    )
    (net (code "37") (name "/WIFI_TX") (class "Default")
      (node (ref "R20") (pin "1") (pinfunction "1_1") (pintype "passive"))
      (node (ref "U$13") (pin "31") (pinfunction "PA10_31") (pintype "bidirectional"))
    )
    (net (code "38") (name "GND") (class "Default")
      (node (ref "C1") (pin "2") (pinfunction "2_2") (pintype "passive"))
      (node (ref "C12") (pin "1") (pinfunction "1_1") (pintype "passive"))
      (node (ref "C2") (pin "2") (pinfunction "2_2") (pintype "passive"))
      (node (ref "C23") (pin "2") (pinfunction "2_2") (pintype "passive"))
      (node (ref "C24") (pin "2") (pinfunction "2_2") (pintype "passive"))
      (node (ref "C25") (pin "2") (pinfunction "2_2") (pintype "passive"))
      (node (ref "C26") (pin "2") (pinfunction "2_2") (pintype "passive"))
      (node (ref "C27") (pin "C") (pinfunction "-_C") (pintype "passive"))
      (node (ref "C29") (pin "2") (pinfunction "2_2") (pintype "passive"))
      (node (ref "C3") (pin "2") (pinfunction "2_2") (pintype "passive"))
      (node (ref "C31") (pin "2") (pinfunction "2_2") (pintype "passive"))
      (node (ref "C32") (pin "2") (pinfunction "2_2") (pintype "passive"))
      (node (ref "C34") (pin "2") (pinfunction "2_2") (pintype "passive"))
      (node (ref "C35") (pin "2") (pinfunction "2_2") (pintype "passive"))
      (node (ref "C36") (pin "2") (pinfunction "2_2") (pintype "passive"))
      (node (ref "C37") (pin "2") (pinfunction "2_2") (pintype "passive"))
      (node (ref "C38") (pin "2") (pinfunction "2_2") (pintype "passive"))
      (node (ref "C4") (pin "2") (pinfunction "2_2") (pintype "passive"))
      (node (ref "C42") (pin "2") (pinfunction "2_2") (pintype "passive"))
      (node (ref "C44") (pin "2") (pinfunction "2_2") (pintype "passive"))
      (node (ref "C5") (pin "2") (pinfunction "2_2") (pintype "passive"))
      (node (ref "C6") (pin "2") (pinfunction "2_2") (pintype "passive"))
      (node (ref "C7") (pin "2") (pinfunction "2_2") (pintype "passive"))
      (node (ref "C8") (pin "2") (pinfunction "2_2") (pintype "passive"))
      (node (ref "C9") (pin "2") (pinfunction "2_2") (pintype "passive"))
      (node (ref "JP1") (pin "1") (pinfunction "1_1") (pintype "passive"))
      (node (ref "JP4") (pin "P$2") (pinfunction "2_P$2") (pintype "bidirectional"))
      (node (ref "JP4") (pin "P$4") (pinfunction "4_P$4") (pintype "bidirectional"))
      (node (ref "LED5") (pin "C") (pinfunction "C_C") (pintype "passive"))
      (node (ref "P1") (pin "1") (pinfunction "1_1") (pintype "passive"))
      (node (ref "Q2") (pin "2") (pinfunction "S_2") (pintype "passive"))
      (node (ref "Q3") (pin "2") (pinfunction "S_2") (pintype "passive"))
      (node (ref "Q4") (pin "2") (pinfunction "S_2") (pintype "passive"))
      (node (ref "Q7") (pin "2") (pinfunction "S_2") (pintype "passive"))
      (node (ref "Q8") (pin "2") (pinfunction "S_2") (pintype "passive"))
      (node (ref "Q9") (pin "2") (pinfunction "S_2") (pintype "passive"))
      (node (ref "R1") (pin "2") (pinfunction "2_2") (pintype "passive"))
      (node (ref "R12") (pin "1") (pinfunction "1_1") (pintype "passive"))
      (node (ref "R13") (pin "1") (pinfunction "1_1") (pintype "passive"))
      (node (ref "R14") (pin "1") (pinfunction "1_1") (pintype "passive"))
      (node (ref "R16") (pin "1") (pinfunction "1_1") (pintype "passive"))
      (node (ref "R21") (pin "1") (pinfunction "1_1") (pintype "passive"))
      (node (ref "R23") (pin "1") (pinfunction "1_1") (pintype "passive"))
      (node (ref "R25") (pin "1") (pinfunction "1_1") (pintype "passive"))
      (node (ref "R26") (pin "1") (pinfunction "1_1") (pintype "passive"))
      (node (ref "R29") (pin "1") (pinfunction "1_1") (pintype "passive"))
      (node (ref "R57") (pin "1") (pinfunction "1_1") (pintype "passive"))
      (node (ref "R6") (pin "1") (pinfunction "1_1") (pintype "passive"))
      (node (ref "R62") (pin "1") (pinfunction "1_1") (pintype "passive"))
      (node (ref "R63") (pin "1") (pinfunction "1_1") (pintype "passive"))
      (node (ref "R7") (pin "1") (pinfunction "1_1") (pintype "passive"))
      (node (ref "R8") (pin "1") (pinfunction "1_1") (pintype "passive"))
      (node (ref "R9") (pin "1") (pinfunction "1_1") (pintype "passive"))
      (node (ref "U$13") (pin "23") (pinfunction "VSS_23") (pintype "bidirectional"))
      (node (ref "U$13") (pin "35") (pinfunction "VSS/1_35") (pintype "bidirectional"))
      (node (ref "U$13") (pin "47") (pinfunction "VSS/2_47") (pintype "bidirectional"))
      (node (ref "U$13") (pin "8") (pinfunction "VSSA_8") (pintype "bidirectional"))
      (node (ref "U$2") (pin "P$14") (pinfunction "14-GND_P$14") (pintype "bidirectional"))
      (node (ref "U$2") (pin "P$20") (pinfunction "20-GND_P$20") (pintype "bidirectional"))
      (node (ref "U$2") (pin "P$25") (pinfunction "25-GND_P$25") (pintype "bidirectional"))
      (node (ref "U$2") (pin "P$30") (pinfunction "30-GND_P$30") (pintype "bidirectional"))
      (node (ref "U$2") (pin "P$34") (pinfunction "34-GND_P$34") (pintype "bidirectional"))
      (node (ref "U$2") (pin "P$39") (pinfunction "39-GND_P$39") (pintype "bidirectional"))
      (node (ref "U$2") (pin "P$6") (pinfunction "6-GND_P$6") (pintype "bidirectional"))
      (node (ref "U$2") (pin "P$9") (pinfunction "9-GND_P$9") (pintype "bidirectional"))
      (node (ref "U$7") (pin "3") (pinfunction "GND_3") (pintype "bidirectional"))
      (node (ref "U$9") (pin "5") (pinfunction "5_5") (pintype "bidirectional"))
      (node (ref "U1") (pin "1") (pinfunction "GND_1") (pintype "passive"))
      (node (ref "U10") (pin "1") (pinfunction "GND_1") (pintype "power_in"))
      (node (ref "U2") (pin "2") (pinfunction "GND_(TAB)_2") (pintype "passive"))
      (node (ref "U2") (pin "4") (pinfunction "GND_(TAB)_2_4") (pintype "passive"))
      (node (ref "U3") (pin "4") (pinfunction "VSS_4") (pintype "bidirectional"))
      (node (ref "U7") (pin "2") (pinfunction "2_2") (pintype "power_in"))
      (node (ref "U8") (pin "1") (pinfunction "P3B_1") (pintype "bidirectional"))
      (node (ref "U8") (pin "16") (pinfunction "P2B_16") (pintype "bidirectional"))
      (node (ref "U8") (pin "17") (pinfunction "P2W_17") (pintype "bidirectional"))
      (node (ref "U8") (pin "2") (pinfunction "HVC/AO_2") (pintype "input"))
      (node (ref "U8") (pin "20") (pinfunction "P3W_20") (pintype "bidirectional"))
      (node (ref "U8") (pin "21") (pinfunction "EP_21") (pintype "bidirectional"))
      (node (ref "U8") (pin "5") (pinfunction "VSS_5") (pintype "power_in"))
      (node (ref "U8") (pin "6") (pinfunction "P1B_6") (pintype "bidirectional"))
      (node (ref "U8") (pin "7") (pinfunction "P1W_7") (pintype "bidirectional"))
      (node (ref "Y1") (pin "2") (pinfunction "2_2") (pintype "power_in"))
    )
    (net (code "39") (name "Net-(C27-+)") (class "Default")
      (node (ref "C27") (pin "A") (pinfunction "+_A") (pintype "passive"))
      (node (ref "JP4") (pin "P$1") (pinfunction "1_P$1") (pintype "bidirectional"))
      (node (ref "R46") (pin "1") (pinfunction "1_1") (pintype "passive"))
    )
    (net (code "40") (name "Net-(LED1-BLUE_A)") (class "Default")
      (node (ref "LED1") (pin "3") (pinfunction "BLUE_A_3") (pintype "bidirectional"))
      (node (ref "R51") (pin "2") (pinfunction "2_2") (pintype "passive"))
    )
    (net (code "41") (name "Net-(LED1-BLUE_C)") (class "Default")
      (node (ref "LED1") (pin "4") (pinfunction "BLUE_C_4") (pintype "bidirectional"))
      (node (ref "Q2") (pin "3") (pinfunction "D_3") (pintype "passive"))
    )
    (net (code "42") (name "Net-(LED1-GREEN_A)") (class "Default")
      (node (ref "LED1") (pin "1") (pinfunction "GREEN_A_1") (pintype "bidirectional"))
      (node (ref "R50") (pin "2") (pinfunction "2_2") (pintype "passive"))
    )
    (net (code "43") (name "Net-(LED1-GREEN_C)") (class "Default")
      (node (ref "LED1") (pin "6") (pinfunction "GREEN_C_6") (pintype "bidirectional"))
      (node (ref "Q3") (pin "3") (pinfunction "D_3") (pintype "passive"))
    )
    (net (code "44") (name "Net-(LED1-RED_A)") (class "Default")
      (node (ref "LED1") (pin "2") (pinfunction "RED_A_2") (pintype "bidirectional"))
      (node (ref "R49") (pin "2") (pinfunction "2_2") (pintype "passive"))
    )
    (net (code "45") (name "Net-(LED1-RED_C)") (class "Default")
      (node (ref "LED1") (pin "5") (pinfunction "RED_C_5") (pintype "bidirectional"))
      (node (ref "Q4") (pin "3") (pinfunction "D_3") (pintype "passive"))
    )
    (net (code "46") (name "Net-(LED5-PadA)") (class "Default")
      (node (ref "LED5") (pin "A") (pinfunction "A_A") (pintype "passive"))
      (node (ref "R40") (pin "2") (pinfunction "2_2") (pintype "passive"))
    )
    (net (code "47") (name "Net-(P1-Pad5)") (class "Default")
      (node (ref "P1") (pin "5") (pinfunction "5_5") (pintype "passive"))
      (node (ref "R12") (pin "2") (pinfunction "2_2") (pintype "passive"))
    )
    (net (code "48") (name "Net-(Q7-D)") (class "Default")
      (node (ref "J1") (pin "5") (pinfunction "H_5") (pintype "bidirectional"))
      (node (ref "Q7") (pin "3") (pinfunction "D_3") (pintype "passive"))
      (node (ref "U4") (pin "5") (pinfunction "H2_5") (pintype "bidirectional"))
    )
    (net (code "49") (name "Net-(Q8-D)") (class "Default")
      (node (ref "J2") (pin "5") (pinfunction "H_5") (pintype "bidirectional"))
      (node (ref "Q8") (pin "3") (pinfunction "D_3") (pintype "passive"))
      (node (ref "U5") (pin "5") (pinfunction "H2_5") (pintype "bidirectional"))
    )
    (net (code "50") (name "Net-(Q9-D)") (class "Default")
      (node (ref "J3") (pin "5") (pinfunction "H_5") (pintype "bidirectional"))
      (node (ref "Q9") (pin "3") (pinfunction "D_3") (pintype "passive"))
      (node (ref "U6") (pin "5") (pinfunction "H2_5") (pintype "bidirectional"))
    )
    (net (code "51") (name "Net-(R17-Pad1)") (class "Default")
      (node (ref "R17") (pin "1") (pinfunction "1_1") (pintype "passive"))
      (node (ref "U7") (pin "4") (pinfunction "4_4") (pintype "bidirectional"))
    )
    (net (code "52") (name "Net-(R18-Pad1)") (class "Default")
      (node (ref "R18") (pin "1") (pinfunction "1_1") (pintype "passive"))
      (node (ref "U7") (pin "6") (pinfunction "6_6") (pintype "bidirectional"))
    )
    (net (code "53") (name "Net-(R26-Pad2)") (class "Default")
      (node (ref "R26") (pin "2") (pinfunction "2_2") (pintype "passive"))
      (node (ref "S2") (pin "2") (pinfunction "2_2") (pintype "passive"))
    )
    (net (code "54") (name "Net-(U$2-8-TX)") (class "Default")
      (node (ref "R20") (pin "2") (pinfunction "2_2") (pintype "passive"))
      (node (ref "U$2") (pin "P$8") (pinfunction "8-TX_P$8") (pintype "bidirectional"))
    )
    (net (code "55") (name "Net-(U$2-10-RX)") (class "Default")
      (node (ref "R19") (pin "2") (pinfunction "2_2") (pintype "passive"))
      (node (ref "U$2") (pin "P$10") (pinfunction "10-RX_P$10") (pintype "bidirectional"))
    )
    (net (code "56") (name "Net-(U$13-PA0)") (class "Default")
      (node (ref "C3") (pin "1") (pinfunction "1_1") (pintype "passive"))
      (node (ref "R57") (pin "2") (pinfunction "2_2") (pintype "passive"))
      (node (ref "R64") (pin "1") (pinfunction "1_1") (pintype "passive"))
      (node (ref "U$13") (pin "10") (pinfunction "PA0_10") (pintype "bidirectional"))
    )
    (net (code "57") (name "Net-(U$13-PA1)") (class "Default")
      (node (ref "C6") (pin "1") (pinfunction "1_1") (pintype "passive"))
      (node (ref "R62") (pin "2") (pinfunction "2_2") (pintype "passive"))
      (node (ref "R66") (pin "1") (pinfunction "1_1") (pintype "passive"))
      (node (ref "U$13") (pin "11") (pinfunction "PA1_11") (pintype "bidirectional"))
    )
    (net (code "58") (name "Net-(U$13-PA2)") (class "Default")
      (node (ref "C7") (pin "1") (pinfunction "1_1") (pintype "passive"))
      (node (ref "R63") (pin "2") (pinfunction "2_2") (pintype "passive"))
      (node (ref "R65") (pin "1") (pinfunction "1_1") (pintype "passive"))
      (node (ref "U$13") (pin "12") (pinfunction "PA2_12") (pintype "bidirectional"))
    )
    (net (code "59") (name "Net-(U3-#HOLD{slash}IO3)") (class "Default")
      (node (ref "R11") (pin "1") (pinfunction "1_1") (pintype "passive"))
      (node (ref "U3") (pin "7") (pinfunction "#HOLD/IO3_7") (pintype "bidirectional"))
    )
    (net (code "60") (name "Net-(U3-#WP{slash}IO2)") (class "Default")
      (node (ref "R5") (pin "1") (pinfunction "1_1") (pintype "passive"))
      (node (ref "U3") (pin "3") (pinfunction "#WP/IO2_3") (pintype "bidirectional"))
    )
    (net (code "61") (name "Net-(U8-WP)") (class "Default")
      (node (ref "R27") (pin "1") (pinfunction "1_1") (pintype "passive"))
      (node (ref "U8") (pin "12") (pinfunction "WP_12") (pintype "input"))
    )
    (net (code "62") (name "Net-(U10-EN)") (class "Default")
      (node (ref "C5") (pin "1") (pinfunction "1_1") (pintype "passive"))
      (node (ref "R28") (pin "1") (pinfunction "1_1") (pintype "passive"))
      (node (ref "U10") (pin "7") (pinfunction "VREF_B_7") (pintype "output"))
      (node (ref "U10") (pin "8") (pinfunction "EN_8") (pintype "output"))
    )
    (net (code "63") (name "unconnected-(P1-Pad2)") (class "Default")
      (node (ref "P1") (pin "2") (pinfunction "2_2") (pintype "passive"))
    )
    (net (code "64") (name "unconnected-(U$2-1-3V3-PadP$1)") (class "Default")
      (node (ref "U$2") (pin "P$1") (pinfunction "1-3V3_P$1") (pintype "bidirectional"))
    )
    (net (code "65") (name "unconnected-(U$2-7-GPIO4-PadP$7)") (class "Default")
      (node (ref "U$2") (pin "P$7") (pinfunction "7-GPIO4_P$7") (pintype "bidirectional"))
    )
    (net (code "66") (name "unconnected-(U$2-11-GPIO17-PadP$11)") (class "Default")
      (node (ref "U$2") (pin "P$11") (pinfunction "11-GPIO17_P$11") (pintype "bidirectional"))
    )
    (net (code "67") (name "unconnected-(U$2-12-GPIO18-PadP$12)") (class "Default")
      (node (ref "U$2") (pin "P$12") (pinfunction "12-GPIO18_P$12") (pintype "bidirectional"))
    )
    (net (code "68") (name "unconnected-(U$2-13-GPIO27-PadP$13)") (class "Default")
      (node (ref "U$2") (pin "P$13") (pinfunction "13-GPIO27_P$13") (pintype "bidirectional"))
    )
    (net (code "69") (name "unconnected-(U$2-15-GPIO22-PadP$15)") (class "Default")
      (node (ref "U$2") (pin "P$15") (pinfunction "15-GPIO22_P$15") (pintype "bidirectional"))
    )
    (net (code "70") (name "unconnected-(U$2-17-3V3-PadP$17)") (class "Default")
      (node (ref "U$2") (pin "P$17") (pinfunction "17-3V3_P$17") (pintype "bidirectional"))
    )
    (net (code "71") (name "unconnected-(U$2-19-SPI-MOSI{slash}GPIO10-PadP$19)") (class "Default")
      (node (ref "U$2") (pin "P$19") (pinfunction "19-SPI-MOSI/GPIO10_P$19") (pintype "bidirectional"))
    )
    (net (code "72") (name "unconnected-(U$2-21-SPI-MISO{slash}GPIO9-PadP$21)") (class "Default")
      (node (ref "U$2") (pin "P$21") (pinfunction "21-SPI-MISO/GPIO9_P$21") (pintype "bidirectional"))
    )
    (net (code "73") (name "unconnected-(U$2-23-SPI-SCLK{slash}GPIO11-PadP$23)") (class "Default")
      (node (ref "U$2") (pin "P$23") (pinfunction "23-SPI-SCLK/GPIO11_P$23") (pintype "bidirectional"))
    )
    (net (code "74") (name "unconnected-(U$2-24-GPIO8-PadP$24)") (class "Default")
      (node (ref "U$2") (pin "P$24") (pinfunction "24-GPIO8_P$24") (pintype "bidirectional"))
    )
    (net (code "75") (name "unconnected-(U$2-26-GPIO7-PadP$26)") (class "Default")
      (node (ref "U$2") (pin "P$26") (pinfunction "26-GPIO7_P$26") (pintype "bidirectional"))
    )
    (net (code "76") (name "unconnected-(U$2-27-ID_SD-PadP$27)") (class "Default")
      (node (ref "U$2") (pin "P$27") (pinfunction "27-ID_SD_P$27") (pintype "bidirectional"))
    )
    (net (code "77") (name "unconnected-(U$2-28-ID_SC-PadP$28)") (class "Default")
      (node (ref "U$2") (pin "P$28") (pinfunction "28-ID_SC_P$28") (pintype "bidirectional"))
    )
    (net (code "78") (name "unconnected-(U$2-29-GPIO5-PadP$29)") (class "Default")
      (node (ref "U$2") (pin "P$29") (pinfunction "29-GPIO5_P$29") (pintype "bidirectional"))
    )
    (net (code "79") (name "unconnected-(U$2-31-GPIO6-PadP$31)") (class "Default")
      (node (ref "U$2") (pin "P$31") (pinfunction "31-GPIO6_P$31") (pintype "bidirectional"))
    )
    (net (code "80") (name "unconnected-(U$2-32-GPIO12-PadP$32)") (class "Default")
      (node (ref "U$2") (pin "P$32") (pinfunction "32-GPIO12_P$32") (pintype "bidirectional"))
    )
    (net (code "81") (name "unconnected-(U$2-33-GPIO13-PadP$33)") (class "Default")
      (node (ref "U$2") (pin "P$33") (pinfunction "33-GPIO13_P$33") (pintype "bidirectional"))
    )
    (net (code "82") (name "unconnected-(U$2-35-GPIO19-PadP$35)") (class "Default")
      (node (ref "U$2") (pin "P$35") (pinfunction "35-GPIO19_P$35") (pintype "bidirectional"))
    )
    (net (code "83") (name "unconnected-(U$2-36-GPIO16-PadP$36)") (class "Default")
      (node (ref "U$2") (pin "P$36") (pinfunction "36-GPIO16_P$36") (pintype "bidirectional"))
    )
    (net (code "84") (name "unconnected-(U$2-37-GPIO26-PadP$37)") (class "Default")
      (node (ref "U$2") (pin "P$37") (pinfunction "37-GPIO26_P$37") (pintype "bidirectional"))
    )
    (net (code "85") (name "unconnected-(U$2-38-GPIO20-PadP$38)") (class "Default")
      (node (ref "U$2") (pin "P$38") (pinfunction "38-GPIO20_P$38") (pintype "bidirectional"))
    )
    (net (code "86") (name "unconnected-(U$2-40-GPIO21-PadP$40)") (class "Default")
      (node (ref "U$2") (pin "P$40") (pinfunction "40-GPIO21_P$40") (pintype "bidirectional"))
    )
    (net (code "87") (name "unconnected-(U$7-GND{slash}+5V_USB-Pad5)") (class "Default")
      (node (ref "U$7") (pin "5") (pinfunction "GND/+5V_USB_5") (pintype "bidirectional"))
    )
    (net (code "88") (name "unconnected-(U$7-N{slash}C-Pad8)") (class "Default")
      (node (ref "U$7") (pin "8") (pinfunction "N/C_8") (pintype "bidirectional"))
    )
    (net (code "89") (name "unconnected-(U$7-RESET-Pad10)") (class "Default")
      (node (ref "U$7") (pin "10") (pinfunction "RESET_10") (pintype "bidirectional"))
    )
    (net (code "90") (name "unconnected-(U$7-RTCLK-Pad7)") (class "Default")
      (node (ref "U$7") (pin "7") (pinfunction "RTCLK_7") (pintype "bidirectional"))
    )
    (net (code "91") (name "unconnected-(U$7-SWO-Pad6)") (class "Default")
      (node (ref "U$7") (pin "6") (pinfunction "SWO_6") (pintype "bidirectional"))
    )
    (net (code "92") (name "unconnected-(U$9-Pad4)") (class "Default")
      (node (ref "U$9") (pin "4") (pinfunction "4_4") (pintype "bidirectional"))
    )
    (net (code "93") (name "unconnected-(U$13-PA8-Pad29)") (class "Default")
      (node (ref "U$13") (pin "29") (pinfunction "PA8_29") (pintype "bidirectional"))
    )
    (net (code "94") (name "unconnected-(U$13-PB2-Pad20)") (class "Default")
      (node (ref "U$13") (pin "20") (pinfunction "PB2_20") (pintype "bidirectional"))
    )
    (net (code "95") (name "unconnected-(U$13-PB3-Pad39)") (class "Default")
      (node (ref "U$13") (pin "39") (pinfunction "PB3_39") (pintype "bidirectional"))
    )
    (net (code "96") (name "unconnected-(U$13-PB4-Pad40)") (class "Default")
      (node (ref "U$13") (pin "40") (pinfunction "PB4_40") (pintype "bidirectional"))
    )
    (net (code "97") (name "unconnected-(U$13-PB5-Pad41)") (class "Default")
      (node (ref "U$13") (pin "41") (pinfunction "PB5_41") (pintype "bidirectional"))
    )
    (net (code "98") (name "unconnected-(U$13-PB10-Pad21)") (class "Default")
      (node (ref "U$13") (pin "21") (pinfunction "PB10_21") (pintype "bidirectional"))
    )
    (net (code "99") (name "unconnected-(U$13-PB11-Pad22)") (class "Default")
      (node (ref "U$13") (pin "22") (pinfunction "PB11_22") (pintype "bidirectional"))
    )
    (net (code "100") (name "unconnected-(U$13-PB12-Pad25)") (class "Default")
      (node (ref "U$13") (pin "25") (pinfunction "PB12_25") (pintype "bidirectional"))
    )
    (net (code "101") (name "unconnected-(U$13-PC13-Pad2)") (class "Default")
      (node (ref "U$13") (pin "2") (pinfunction "PC13_2") (pintype "bidirectional"))
    )
    (net (code "102") (name "unconnected-(U$13-PC14-Pad3)") (class "Default")
      (node (ref "U$13") (pin "3") (pinfunction "PC14_3") (pintype "bidirectional"))
    )
    (net (code "103") (name "unconnected-(U8-P0A-Pad9)") (class "Default")
      (node (ref "U8") (pin "9") (pinfunction "P0A_9") (pintype "bidirectional"))
    )
    (net (code "104") (name "unconnected-(U8-P0B-Pad11)") (class "Default")
      (node (ref "U8") (pin "11") (pinfunction "P0B_11") (pintype "bidirectional"))
    )
    (net (code "105") (name "unconnected-(U8-P0W-Pad10)") (class "Default")
      (node (ref "U8") (pin "10") (pinfunction "P0W_10") (pintype "bidirectional"))
    )
  )
)
